# main.net
KiCad netlist of a schematic drawn in Altium Designer
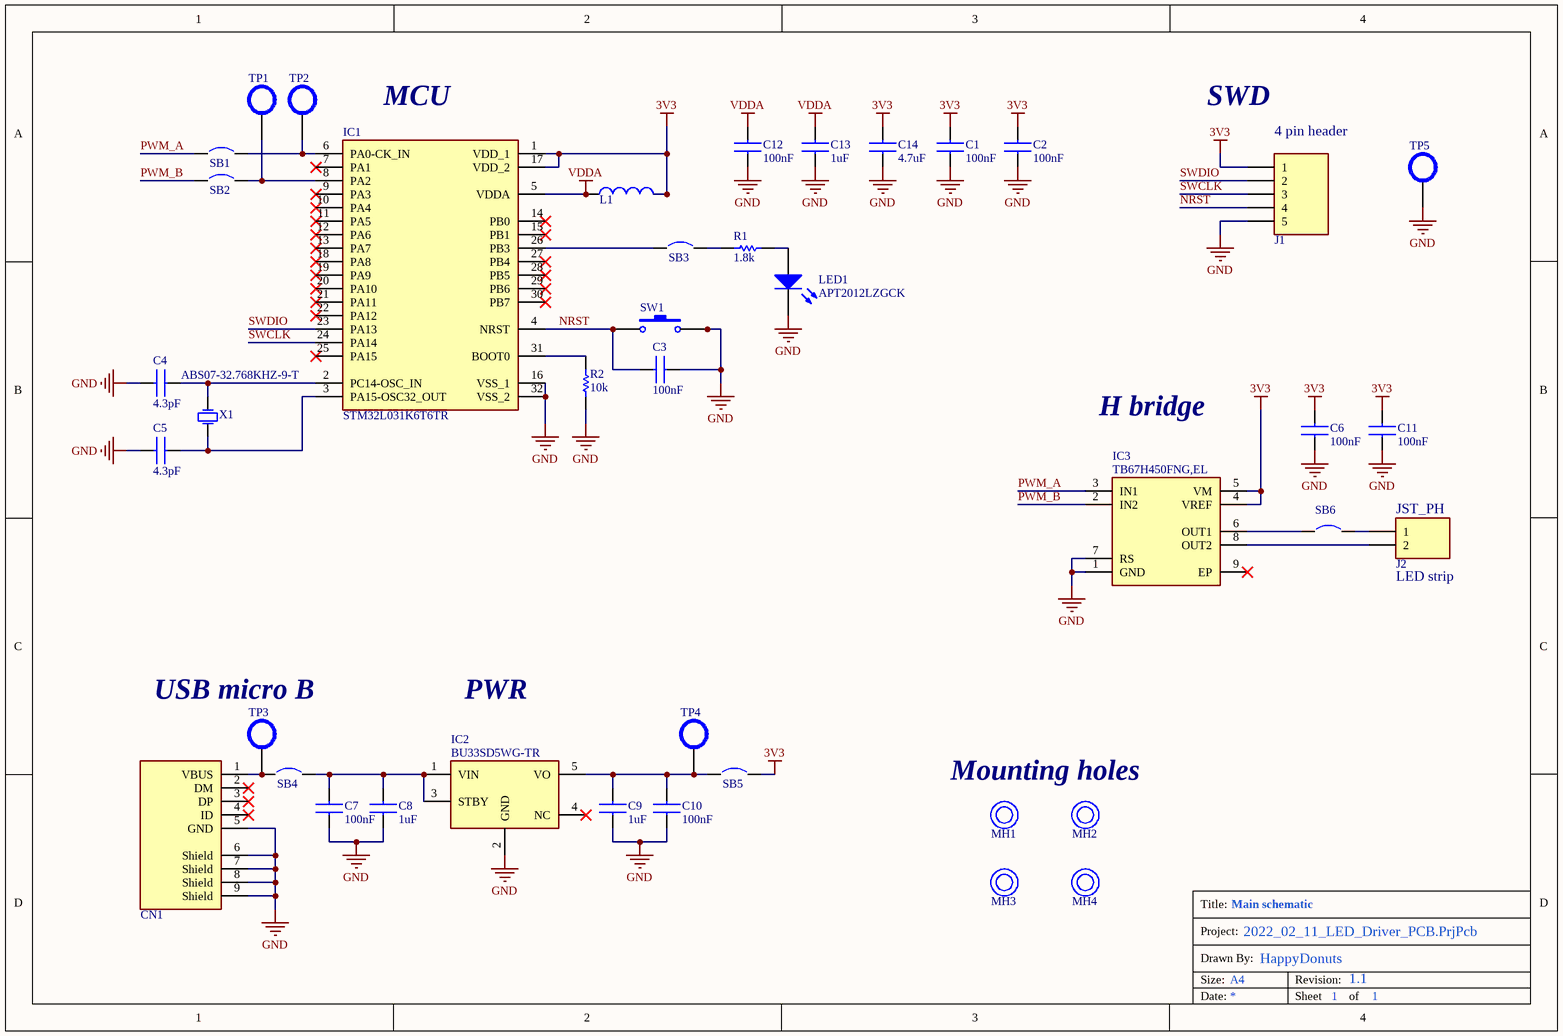
[diagram p0: main.SchDoc]

(export (version "E")
  (design (tool "Eeschema 10.0.6"))
  (components
    (comp (ref "C1")
      (value "100nF")
      (footprint "PcbLib1:CAPC2012X94N")
      (description "Capacitor")
      (fields
        (field (name "MANUFACTURER_PART_NUMBER") "C0805C104K5RAC7411")
        (field (name "MOUSER PART NUMBER") "80-C0805C104K5RACLR")
      )
      (libsource (lib "Schlib1") (part "C0805C104K5RAC7411"))
    )
    (comp (ref "C2")
      (value "100nF")
      (footprint "PcbLib1:CAPC2012X94N")
      (description "Capacitor")
      (fields
        (field (name "MANUFACTURER_PART_NUMBER") "C0805C104K5RAC7411")
        (field (name "MOUSER PART NUMBER") "80-C0805C104K5RACLR")
      )
      (libsource (lib "Schlib1") (part "C0805C104K5RAC7411"))
    )
    (comp (ref "C3")
      (value "100nF")
      (footprint "PcbLib1:CAPC2012X94N")
      (description "Capacitor")
      (fields
        (field (name "MANUFACTURER_PART_NUMBER") "C0805C104K5RAC7411")
        (field (name "MOUSER PART NUMBER") "80-C0805C104K5RACLR")
      )
      (libsource (lib "Schlib1") (part "C0805C104K5RAC7411"))
    )
    (comp (ref "C4")
      (value "4.3pF")
      (footprint "PcbLib1:CAPC2012X94N")
      (description "Capacitor")
      (fields (field (name "MANUFACTURER_PART_NUMBER") "08055A4R3CAT2A"))
      (libsource (lib "Schlib1") (part "08055A4R3CAT2A"))
    )
    (comp (ref "C5")
      (value "4.3pF")
      (footprint "PcbLib1:CAPC2012X94N")
      (description "Capacitor")
      (fields (field (name "MANUFACTURER_PART_NUMBER") "08055A4R3CAT2A"))
      (libsource (lib "Schlib1") (part "08055A4R3CAT2A"))
    )
    (comp (ref "C6")
      (value "100nF")
      (footprint "PcbLib1:CAPC2012X94N")
      (description "Capacitor")
      (fields
        (field (name "MANUFACTURER_PART_NUMBER") "C0805C104K5RAC7411")
        (field (name "MOUSER PART NUMBER") "80-C0805C104K5RACLR")
      )
      (libsource (lib "Schlib1") (part "C0805C104K5RAC7411"))
    )
    (comp (ref "C7")
      (value "100nF")
      (footprint "PcbLib1:CAPC2012X94N")
      (description "Capacitor")
      (fields
        (field (name "MANUFACTURER_PART_NUMBER") "C0805C104K5RAC7411")
        (field (name "MOUSER PART NUMBER") "80-C0805C104K5RACLR")
      )
      (libsource (lib "Schlib1") (part "C0805C104K5RAC7411"))
    )
    (comp (ref "C8")
      (value "1uF")
      (footprint "PcbLib1:CAPC2012X135N")
      (description "Capacitor")
      (fields
        (field (name "MANUFACTURER_PART_NUMBER") "885012107015")
        (field (name "MOUSER PART NUMBER") "710-885012107015")
      )
      (libsource (lib "Schlib1") (part "885012107015"))
    )
    (comp (ref "C9")
      (value "1uF")
      (footprint "PcbLib1:CAPC2012X135N")
      (description "Capacitor")
      (fields
        (field (name "MANUFACTURER_PART_NUMBER") "885012107015")
        (field (name "MOUSER PART NUMBER") "710-885012107015")
      )
      (libsource (lib "Schlib1") (part "885012107015"))
    )
    (comp (ref "C10")
      (value "100nF")
      (footprint "PcbLib1:CAPC2012X94N")
      (description "Capacitor")
      (fields
        (field (name "MANUFACTURER_PART_NUMBER") "C0805C104K5RAC7411")
        (field (name "MOUSER PART NUMBER") "80-C0805C104K5RACLR")
      )
      (libsource (lib "Schlib1") (part "C0805C104K5RAC7411"))
    )
    (comp (ref "C11")
      (value "100nF")
      (footprint "PcbLib1:CAPC2012X94N")
      (description "Capacitor")
      (fields
        (field (name "MANUFACTURER_PART_NUMBER") "C0805C104K5RAC7411")
        (field (name "MOUSER PART NUMBER") "80-C0805C104K5RACLR")
      )
      (libsource (lib "Schlib1") (part "C0805C104K5RAC7411"))
    )
    (comp (ref "C12")
      (value "100nF")
      (footprint "PcbLib1:CAPC2012X94N")
      (description "Capacitor")
      (fields
        (field (name "MANUFACTURER_PART_NUMBER") "C0805C104K5RAC7411")
        (field (name "MOUSER PART NUMBER") "80-C0805C104K5RACLR")
      )
      (libsource (lib "Schlib1") (part "C0805C104K5RAC7411"))
    )
    (comp (ref "C13")
      (value "1uF")
      (footprint "PcbLib1:CAPC2012X135N")
      (description "Capacitor")
      (fields
        (field (name "MANUFACTURER_PART_NUMBER") "885012107015")
        (field (name "MOUSER PART NUMBER") "710-885012107015")
      )
      (libsource (lib "Schlib1") (part "885012107015"))
    )
    (comp (ref "C14")
      (value "4.7uF")
      (footprint "PcbLib1:CAPC2012X135N")
      (description "Capacitor")
      (fields
        (field (name "MANUFACTURER_PART_NUMBER") "CL21A475KPFNNNE")
        (field (name "MOUSER PART NUMBER") "187-CL21A475KPFNNNE")
      )
      (libsource (lib "Schlib1") (part "CL21A475KPFNNNE"))
    )
    (comp (ref "CN1")
      (value "920-E52A2021S10100")
      (footprint "PcbLib1:USB307530A")
      (description "USB connector")
      (fields (field (name "ARROW PART NUMBER") "TB67H450FNG,EL"))
      (libsource (lib "Schlib1") (part "920-E52A2021S10100"))
    )
    (comp (ref "IC1")
      (value "STM32L031K6T6TR")
      (footprint "PcbLib1:QFP80P900X900X160-32N")
      (description "Integrated Circuit")
      (fields
        (field (name "MOUSER PART NUMBER") "511-STM32L031K6T6TR")
        (field (name "ARROW PART NUMBER") "STM32L031K6T6")
      )
      (libsource (lib "Schlib1") (part "STM32L031K6T6TR"))
    )
    (comp (ref "IC2")
      (value "BU33SD5WG-TR")
      (footprint "PcbLib1:SOT95P280X125-5N")
      (description "Power Supply")
      (fields (field (name "MOUSER PART NUMBER") "755-BU33SD5WG-TR"))
      (libsource (lib "Schlib1") (part "BU33SD5WG-TR"))
    )
    (comp (ref "IC3")
      (value "TB67H450FNG,EL")
      (footprint "PcbLib1:SOIC127P600X175-9N")
      (description "Integrated Circuit")
      (fields (field (name "MOUSER PART NUMBER") "757-TB67H450FNGEL"))
      (libsource (lib "Schlib1") (part "TB67H450FNG,EL"))
    )
    (comp (ref "J1")
      (value "5PIN")
      (footprint "PcbLib1:5PIN")
      (description "Connector")
      (libsource (lib "Schlib1") (part "5PIN"))
    )
    (comp (ref "J2")
      (value "B2B-PH-K-S_LF__SN_")
      (footprint "PcbLib1:SHDR2W50P0X200_1X2_590X450X600P")
      (description "Connector")
      (fields (field (name "MANUFACTURER_PART_NUMBER") "B2B-PH-K-S(LF)(SN)"))
      (libsource (lib "Schlib1") (part "B2B-PH-K-S_LF__SN_"))
    )
    (comp (ref "L1")
      (value "742792030")
      (footprint "PcbLib1:RESC2012X60N")
      (description "Inductor")
      (libsource (lib "Schlib1") (part "742792030"))
    )
    (comp (ref "LED1")
      (value "APT2012LZGCK")
      (footprint "PcbLib1:LEDC2012X85N")
      (description "LED")
      (fields (field (name "MOUSER PART NUMBER") "604-APT2012LZGCK"))
      (libsource (lib "Schlib1") (part "APT2012LZGCK"))
    )
    (comp (ref "MH1")
      (value "MOUNTING_HOLE_NP")
      (footprint "MOUNTING_HOLE_NP")
      (description "Mounting hole")
      (libsource (lib "Schlib1") (part "MOUNTING_HOLE_NP"))
    )
    (comp (ref "MH2")
      (value "MOUNTING_HOLE_NP")
      (footprint "MOUNTING_HOLE_NP")
      (description "Mounting hole")
      (libsource (lib "Schlib1") (part "MOUNTING_HOLE_NP"))
    )
    (comp (ref "MH3")
      (value "MOUNTING_HOLE_NP")
      (footprint "MOUNTING_HOLE_NP")
      (description "Mounting hole")
      (libsource (lib "Schlib1") (part "MOUNTING_HOLE_NP"))
    )
    (comp (ref "MH4")
      (value "MOUNTING_HOLE_NP")
      (footprint "MOUNTING_HOLE_NP")
      (description "Mounting hole")
      (libsource (lib "Schlib1") (part "MOUNTING_HOLE_NP"))
    )
    (comp (ref "R1")
      (value "1.8k")
      (footprint "PcbLib1:RESC2012X60N")
      (description "Resistor")
      (fields
        (field (name "MANUFACTURER_PART_NUMBER") "RC0805FR-071K8L")
        (field (name "MOUSER PART NUMBER") "603-RC0805FR-071K8L")
      )
      (libsource (lib "Schlib1") (part "RC0805FR-071K8L"))
    )
    (comp (ref "R2")
      (value "10k")
      (footprint "PcbLib1:RESC2012X60N")
      (description "Resistor")
      (fields
        (field (name "MANUFACTURER_PART_NUMBER") "RC0805FR-0710KL")
        (field (name "MOUSER PART NUMBER") "603-RC0805FR-0710KL")
      )
      (libsource (lib "Schlib1") (part "RC0805FR-0710KL"))
    )
    (comp (ref "SB1")
      (value "RC0805FR-070RL")
      (footprint "PcbLib1:RESC2012X60N")
      (description "Jumper (0 ohm)")
      (fields (field (name "MOUSER PART NUMBER") "603-RC0805FR-070RL"))
      (libsource (lib "Schlib1") (part "RC0805FR-070RL"))
    )
    (comp (ref "SB2")
      (value "RC0805FR-070RL")
      (footprint "PcbLib1:RESC2012X60N")
      (description "Jumper (0 ohm)")
      (fields (field (name "MOUSER PART NUMBER") "603-RC0805FR-070RL"))
      (libsource (lib "Schlib1") (part "RC0805FR-070RL"))
    )
    (comp (ref "SB3")
      (value "RC0805FR-070RL")
      (footprint "PcbLib1:RESC2012X60N")
      (description "Jumper (0 ohm)")
      (fields (field (name "MOUSER PART NUMBER") "603-RC0805FR-070RL"))
      (libsource (lib "Schlib1") (part "RC0805FR-070RL"))
    )
    (comp (ref "SB4")
      (value "RC0805FR-070RL")
      (footprint "PcbLib1:RESC2012X60N")
      (description "Jumper (0 ohm)")
      (fields (field (name "MOUSER PART NUMBER") "603-RC0805FR-070RL"))
      (libsource (lib "Schlib1") (part "RC0805FR-070RL"))
    )
    (comp (ref "SB5")
      (value "RC0805FR-070RL")
      (footprint "PcbLib1:RESC2012X60N")
      (description "Jumper (0 ohm)")
      (fields (field (name "MOUSER PART NUMBER") "603-RC0805FR-070RL"))
      (libsource (lib "Schlib1") (part "RC0805FR-070RL"))
    )
    (comp (ref "SB6")
      (value "RC0805FR-070RL")
      (footprint "PcbLib1:RESC2012X60N")
      (description "Jumper (0 ohm)")
      (fields (field (name "MOUSER PART NUMBER") "603-RC0805FR-070RL"))
      (libsource (lib "Schlib1") (part "RC0805FR-070RL"))
    )
    (comp (ref "SW1")
      (value "EVP-BT3G4A000")
      (footprint "PcbLib1:EVP-BT3G4A000")
      (description "Tactile switch")
      (libsource (lib "Schlib1") (part "EVP-BT3G4A000"))
    )
    (comp (ref "TP1")
      (value "TEST_POINT")
      (footprint "TEST_POINT")
      (description "Test point")
      (libsource (lib "Schlib1") (part "TEST_POINT"))
    )
    (comp (ref "TP2")
      (value "TEST_POINT")
      (footprint "TEST_POINT")
      (description "Test point")
      (libsource (lib "Schlib1") (part "TEST_POINT"))
    )
    (comp (ref "TP3")
      (value "TEST_POINT")
      (footprint "TEST_POINT")
      (description "Test point")
      (libsource (lib "Schlib1") (part "TEST_POINT"))
    )
    (comp (ref "TP4")
      (value "TEST_POINT")
      (footprint "TEST_POINT")
      (description "Test point")
      (libsource (lib "Schlib1") (part "TEST_POINT"))
    )
    (comp (ref "TP5")
      (value "TEST_POINT")
      (footprint "TEST_POINT")
      (description "Test point")
      (libsource (lib "Schlib1") (part "TEST_POINT"))
    )
    (comp (ref "X1")
      (value "ABS07-32.768KHZ-9-T")
      (footprint "PcbLib1:ABS-07")
      (description "Crystal")
      (fields (field (name "MOUSER PART NUMBER") "815-ABS07-32.768K9T"))
      (libsource (lib "Schlib1") (part "ABS07-32.768KHZ-9-T"))
    )
  )
  (nets
    (net (code "1") (name "/NRST") (class "Default")
      (node (ref "C3") (pin "1") (pinfunction "1_1") (pintype "passive"))
      (node (ref "IC1") (pin "4") (pinfunction "NRST_4") (pintype "passive"))
      (node (ref "J1") (pin "4") (pinfunction "4_4") (pintype "passive"))
      (node (ref "SW1") (pin "1") (pinfunction "1_1") (pintype "passive"))
      (node (ref "SW1") (pin "2") (pinfunction "2_2") (pintype "passive"))
    )
    (net (code "2") (name "/PWM_A") (class "Default")
      (node (ref "IC3") (pin "3") (pinfunction "IN1_3") (pintype "passive"))
      (node (ref "SB1") (pin "1") (pinfunction "1_1") (pintype "passive"))
    )
    (net (code "3") (name "/PWM_B") (class "Default")
      (node (ref "IC3") (pin "2") (pinfunction "IN2_2") (pintype "passive"))
      (node (ref "SB2") (pin "1") (pinfunction "1_1") (pintype "passive"))
    )
    (net (code "4") (name "/SWCLK") (class "Default")
      (node (ref "IC1") (pin "24") (pinfunction "PA14_24") (pintype "passive"))
      (node (ref "J1") (pin "3") (pinfunction "3_3") (pintype "passive"))
    )
    (net (code "5") (name "/SWDIO") (class "Default")
      (node (ref "IC1") (pin "23") (pinfunction "PA13_23") (pintype "passive"))
      (node (ref "J1") (pin "2") (pinfunction "2_2") (pintype "passive"))
    )
    (net (code "6") (name "3V3") (class "Default")
      (node (ref "C1") (pin "2") (pinfunction "2_2") (pintype "passive"))
      (node (ref "C11") (pin "2") (pinfunction "2_2") (pintype "passive"))
      (node (ref "C14") (pin "2") (pinfunction "2_2") (pintype "passive"))
      (node (ref "C2") (pin "2") (pinfunction "2_2") (pintype "passive"))
      (node (ref "C6") (pin "2") (pinfunction "2_2") (pintype "passive"))
      (node (ref "IC1") (pin "1") (pinfunction "VDD_1_1") (pintype "passive"))
      (node (ref "IC1") (pin "17") (pinfunction "VDD_2_17") (pintype "passive"))
      (node (ref "IC3") (pin "4") (pinfunction "VREF_4") (pintype "passive"))
      (node (ref "IC3") (pin "5") (pinfunction "VM_5") (pintype "passive"))
      (node (ref "J1") (pin "1") (pinfunction "1_1") (pintype "passive"))
      (node (ref "L1") (pin "2") (pinfunction "2_2") (pintype "passive"))
      (node (ref "SB5") (pin "2") (pinfunction "2_2") (pintype "passive"))
    )
    (net (code "7") (name "GND") (class "Default")
      (node (ref "C1") (pin "1") (pinfunction "1_1") (pintype "passive"))
      (node (ref "C10") (pin "1") (pinfunction "1_1") (pintype "passive"))
      (node (ref "C11") (pin "1") (pinfunction "1_1") (pintype "passive"))
      (node (ref "C12") (pin "1") (pinfunction "1_1") (pintype "passive"))
      (node (ref "C13") (pin "1") (pinfunction "1_1") (pintype "passive"))
      (node (ref "C14") (pin "1") (pinfunction "1_1") (pintype "passive"))
      (node (ref "C2") (pin "1") (pinfunction "1_1") (pintype "passive"))
      (node (ref "C3") (pin "2") (pinfunction "2_2") (pintype "passive"))
      (node (ref "C4") (pin "1") (pinfunction "1_1") (pintype "passive"))
      (node (ref "C5") (pin "1") (pinfunction "1_1") (pintype "passive"))
      (node (ref "C6") (pin "1") (pinfunction "1_1") (pintype "passive"))
      (node (ref "C7") (pin "1") (pinfunction "1_1") (pintype "passive"))
      (node (ref "C8") (pin "1") (pinfunction "1_1") (pintype "passive"))
      (node (ref "C9") (pin "1") (pinfunction "1_1") (pintype "passive"))
      (node (ref "CN1") (pin "5") (pinfunction "GND_5") (pintype "passive"))
      (node (ref "CN1") (pin "6") (pinfunction "Shield_6") (pintype "passive"))
      (node (ref "CN1") (pin "7") (pinfunction "Shield_7") (pintype "passive"))
      (node (ref "CN1") (pin "8") (pinfunction "Shield_8") (pintype "passive"))
      (node (ref "CN1") (pin "9") (pinfunction "Shield_9") (pintype "passive"))
      (node (ref "IC1") (pin "16") (pinfunction "VSS_1_16") (pintype "passive"))
      (node (ref "IC1") (pin "32") (pinfunction "VSS_2_32") (pintype "passive"))
      (node (ref "IC2") (pin "2") (pinfunction "GND_2") (pintype "passive"))
      (node (ref "IC3") (pin "1") (pinfunction "GND_1") (pintype "passive"))
      (node (ref "IC3") (pin "7") (pinfunction "RS_7") (pintype "passive"))
      (node (ref "J1") (pin "5") (pinfunction "5_5") (pintype "passive"))
      (node (ref "LED1") (pin "2") (pinfunction "A_2") (pintype "passive"))
      (node (ref "R2") (pin "1") (pinfunction "1_1") (pintype "passive"))
      (node (ref "SW1") (pin "3") (pinfunction "3_3") (pintype "passive"))
      (node (ref "SW1") (pin "4") (pinfunction "4_4") (pintype "passive"))
      (node (ref "TP5") (pin "TP") (pinfunction "TP_TP") (pintype "passive"))
    )
    (net (code "8") (name "Net-(CN1-VBUS)") (class "Default")
      (node (ref "CN1") (pin "1") (pinfunction "VBUS_1") (pintype "passive"))
      (node (ref "SB4") (pin "1") (pinfunction "1_1") (pintype "passive"))
      (node (ref "TP3") (pin "TP") (pinfunction "TP_TP") (pintype "passive"))
    )
    (net (code "9") (name "Net-(IC1-BOOT0)") (class "Default")
      (node (ref "IC1") (pin "31") (pinfunction "BOOT0_31") (pintype "passive"))
      (node (ref "R2") (pin "2") (pinfunction "2_2") (pintype "passive"))
    )
    (net (code "10") (name "Net-(IC1-PA0-CK_IN)") (class "Default")
      (node (ref "IC1") (pin "6") (pinfunction "PA0-CK_IN_6") (pintype "passive"))
      (node (ref "SB1") (pin "2") (pinfunction "2_2") (pintype "passive"))
      (node (ref "TP2") (pin "TP") (pinfunction "TP_TP") (pintype "passive"))
    )
    (net (code "11") (name "Net-(IC1-PA2)") (class "Default")
      (node (ref "IC1") (pin "8") (pinfunction "PA2_8") (pintype "passive"))
      (node (ref "SB2") (pin "2") (pinfunction "2_2") (pintype "passive"))
      (node (ref "TP1") (pin "TP") (pinfunction "TP_TP") (pintype "passive"))
    )
    (net (code "12") (name "Net-(IC1-PA15-OSC32_OUT)") (class "Default")
      (node (ref "C5") (pin "2") (pinfunction "2_2") (pintype "passive"))
      (node (ref "IC1") (pin "3") (pinfunction "PA15-OSC32_OUT_3") (pintype "passive"))
      (node (ref "X1") (pin "1") (pinfunction "1_1") (pintype "passive"))
    )
    (net (code "13") (name "Net-(IC1-PB3)") (class "Default")
      (node (ref "IC1") (pin "26") (pinfunction "PB3_26") (pintype "passive"))
      (node (ref "SB3") (pin "1") (pinfunction "1_1") (pintype "passive"))
    )
    (net (code "14") (name "Net-(IC1-PC14-OSC_IN)") (class "Default")
      (node (ref "C4") (pin "2") (pinfunction "2_2") (pintype "passive"))
      (node (ref "IC1") (pin "2") (pinfunction "PC14-OSC_IN_2") (pintype "passive"))
      (node (ref "X1") (pin "2") (pinfunction "2_2") (pintype "passive"))
    )
    (net (code "15") (name "Net-(IC2-STBY)") (class "Default")
      (node (ref "C7") (pin "2") (pinfunction "2_2") (pintype "passive"))
      (node (ref "C8") (pin "2") (pinfunction "2_2") (pintype "passive"))
      (node (ref "IC2") (pin "1") (pinfunction "VIN_1") (pintype "passive"))
      (node (ref "IC2") (pin "3") (pinfunction "STBY_3") (pintype "passive"))
      (node (ref "SB4") (pin "2") (pinfunction "2_2") (pintype "passive"))
    )
    (net (code "16") (name "Net-(IC2-VO)") (class "Default")
      (node (ref "C10") (pin "2") (pinfunction "2_2") (pintype "passive"))
      (node (ref "C9") (pin "2") (pinfunction "2_2") (pintype "passive"))
      (node (ref "IC2") (pin "5") (pinfunction "VO_5") (pintype "passive"))
      (node (ref "SB5") (pin "1") (pinfunction "1_1") (pintype "passive"))
      (node (ref "TP4") (pin "TP") (pinfunction "TP_TP") (pintype "passive"))
    )
    (net (code "17") (name "Net-(IC3-OUT1)") (class "Default")
      (node (ref "IC3") (pin "6") (pinfunction "OUT1_6") (pintype "passive"))
      (node (ref "SB6") (pin "1") (pinfunction "1_1") (pintype "passive"))
    )
    (net (code "18") (name "Net-(IC3-OUT2)") (class "Default")
      (node (ref "IC3") (pin "8") (pinfunction "OUT2_8") (pintype "passive"))
      (node (ref "J2") (pin "2") (pinfunction "2_2") (pintype "passive"))
    )
    (net (code "19") (name "Net-(J2-Pad1)") (class "Default")
      (node (ref "J2") (pin "1") (pinfunction "1_1") (pintype "passive"))
      (node (ref "SB6") (pin "2") (pinfunction "2_2") (pintype "passive"))
    )
    (net (code "20") (name "Net-(LED1-K)") (class "Default")
      (node (ref "LED1") (pin "1") (pinfunction "K_1") (pintype "passive"))
      (node (ref "R1") (pin "2") (pinfunction "2_2") (pintype "passive"))
    )
    (net (code "21") (name "Net-(R1-Pad1)") (class "Default")
      (node (ref "R1") (pin "1") (pinfunction "1_1") (pintype "passive"))
      (node (ref "SB3") (pin "2") (pinfunction "2_2") (pintype "passive"))
    )
    (net (code "22") (name "VDDA") (class "Default")
      (node (ref "C12") (pin "2") (pinfunction "2_2") (pintype "passive"))
      (node (ref "C13") (pin "2") (pinfunction "2_2") (pintype "passive"))
      (node (ref "IC1") (pin "5") (pinfunction "VDDA_5") (pintype "passive"))
      (node (ref "L1") (pin "1") (pinfunction "1_1") (pintype "passive"))
    )
    (net (code "23") (name "unconnected-(CN1-DM-Pad2)") (class "Default")
      (node (ref "CN1") (pin "2") (pinfunction "DM_2") (pintype "passive+no_connect"))
    )
    (net (code "24") (name "unconnected-(CN1-DP-Pad3)") (class "Default")
      (node (ref "CN1") (pin "3") (pinfunction "DP_3") (pintype "passive+no_connect"))
    )
    (net (code "25") (name "unconnected-(CN1-ID-Pad4)") (class "Default")
      (node (ref "CN1") (pin "4") (pinfunction "ID_4") (pintype "passive+no_connect"))
    )
    (net (code "26") (name "unconnected-(IC1-PA1-Pad7)") (class "Default")
      (node (ref "IC1") (pin "7") (pinfunction "PA1_7") (pintype "passive+no_connect"))
    )
    (net (code "27") (name "unconnected-(IC1-PA3-Pad9)") (class "Default")
      (node (ref "IC1") (pin "9") (pinfunction "PA3_9") (pintype "passive+no_connect"))
    )
    (net (code "28") (name "unconnected-(IC1-PA4-Pad10)") (class "Default")
      (node (ref "IC1") (pin "10") (pinfunction "PA4_10") (pintype "passive+no_connect"))
    )
    (net (code "29") (name "unconnected-(IC1-PA5-Pad11)") (class "Default")
      (node (ref "IC1") (pin "11") (pinfunction "PA5_11") (pintype "passive+no_connect"))
    )
    (net (code "30") (name "unconnected-(IC1-PA6-Pad12)") (class "Default")
      (node (ref "IC1") (pin "12") (pinfunction "PA6_12") (pintype "passive+no_connect"))
    )
    (net (code "31") (name "unconnected-(IC1-PA7-Pad13)") (class "Default")
      (node (ref "IC1") (pin "13") (pinfunction "PA7_13") (pintype "passive+no_connect"))
    )
    (net (code "32") (name "unconnected-(IC1-PA8-Pad18)") (class "Default")
      (node (ref "IC1") (pin "18") (pinfunction "PA8_18") (pintype "passive+no_connect"))
    )
    (net (code "33") (name "unconnected-(IC1-PA9-Pad19)") (class "Default")
      (node (ref "IC1") (pin "19") (pinfunction "PA9_19") (pintype "passive+no_connect"))
    )
    (net (code "34") (name "unconnected-(IC1-PA10-Pad20)") (class "Default")
      (node (ref "IC1") (pin "20") (pinfunction "PA10_20") (pintype "passive+no_connect"))
    )
    (net (code "35") (name "unconnected-(IC1-PA11-Pad21)") (class "Default")
      (node (ref "IC1") (pin "21") (pinfunction "PA11_21") (pintype "passive+no_connect"))
    )
    (net (code "36") (name "unconnected-(IC1-PA12-Pad22)") (class "Default")
      (node (ref "IC1") (pin "22") (pinfunction "PA12_22") (pintype "passive+no_connect"))
    )
    (net (code "37") (name "unconnected-(IC1-PA15-Pad25)") (class "Default")
      (node (ref "IC1") (pin "25") (pinfunction "PA15_25") (pintype "passive+no_connect"))
    )
    (net (code "38") (name "unconnected-(IC1-PB0-Pad14)") (class "Default")
      (node (ref "IC1") (pin "14") (pinfunction "PB0_14") (pintype "passive+no_connect"))
    )
    (net (code "39") (name "unconnected-(IC1-PB1-Pad15)") (class "Default")
      (node (ref "IC1") (pin "15") (pinfunction "PB1_15") (pintype "passive+no_connect"))
    )
    (net (code "40") (name "unconnected-(IC1-PB4-Pad27)") (class "Default")
      (node (ref "IC1") (pin "27") (pinfunction "PB4_27") (pintype "passive+no_connect"))
    )
    (net (code "41") (name "unconnected-(IC1-PB5-Pad28)") (class "Default")
      (node (ref "IC1") (pin "28") (pinfunction "PB5_28") (pintype "passive+no_connect"))
    )
    (net (code "42") (name "unconnected-(IC1-PB6-Pad29)") (class "Default")
      (node (ref "IC1") (pin "29") (pinfunction "PB6_29") (pintype "passive+no_connect"))
    )
    (net (code "43") (name "unconnected-(IC1-PB7-Pad30)") (class "Default")
      (node (ref "IC1") (pin "30") (pinfunction "PB7_30") (pintype "passive+no_connect"))
    )
    (net (code "44") (name "unconnected-(IC2-NC-Pad4)") (class "Default")
      (node (ref "IC2") (pin "4") (pinfunction "NC_4") (pintype "passive+no_connect"))
    )
    (net (code "45") (name "unconnected-(IC3-EP-Pad9)") (class "Default")
      (node (ref "IC3") (pin "9") (pinfunction "EP_9") (pintype "passive+no_connect"))
    )
  )
)
